# 780-00055_rev1_Pg1_SCH_NRES_Temp_Meas_8-.net
KiCad netlist of a schematic drawn in Altium Designer
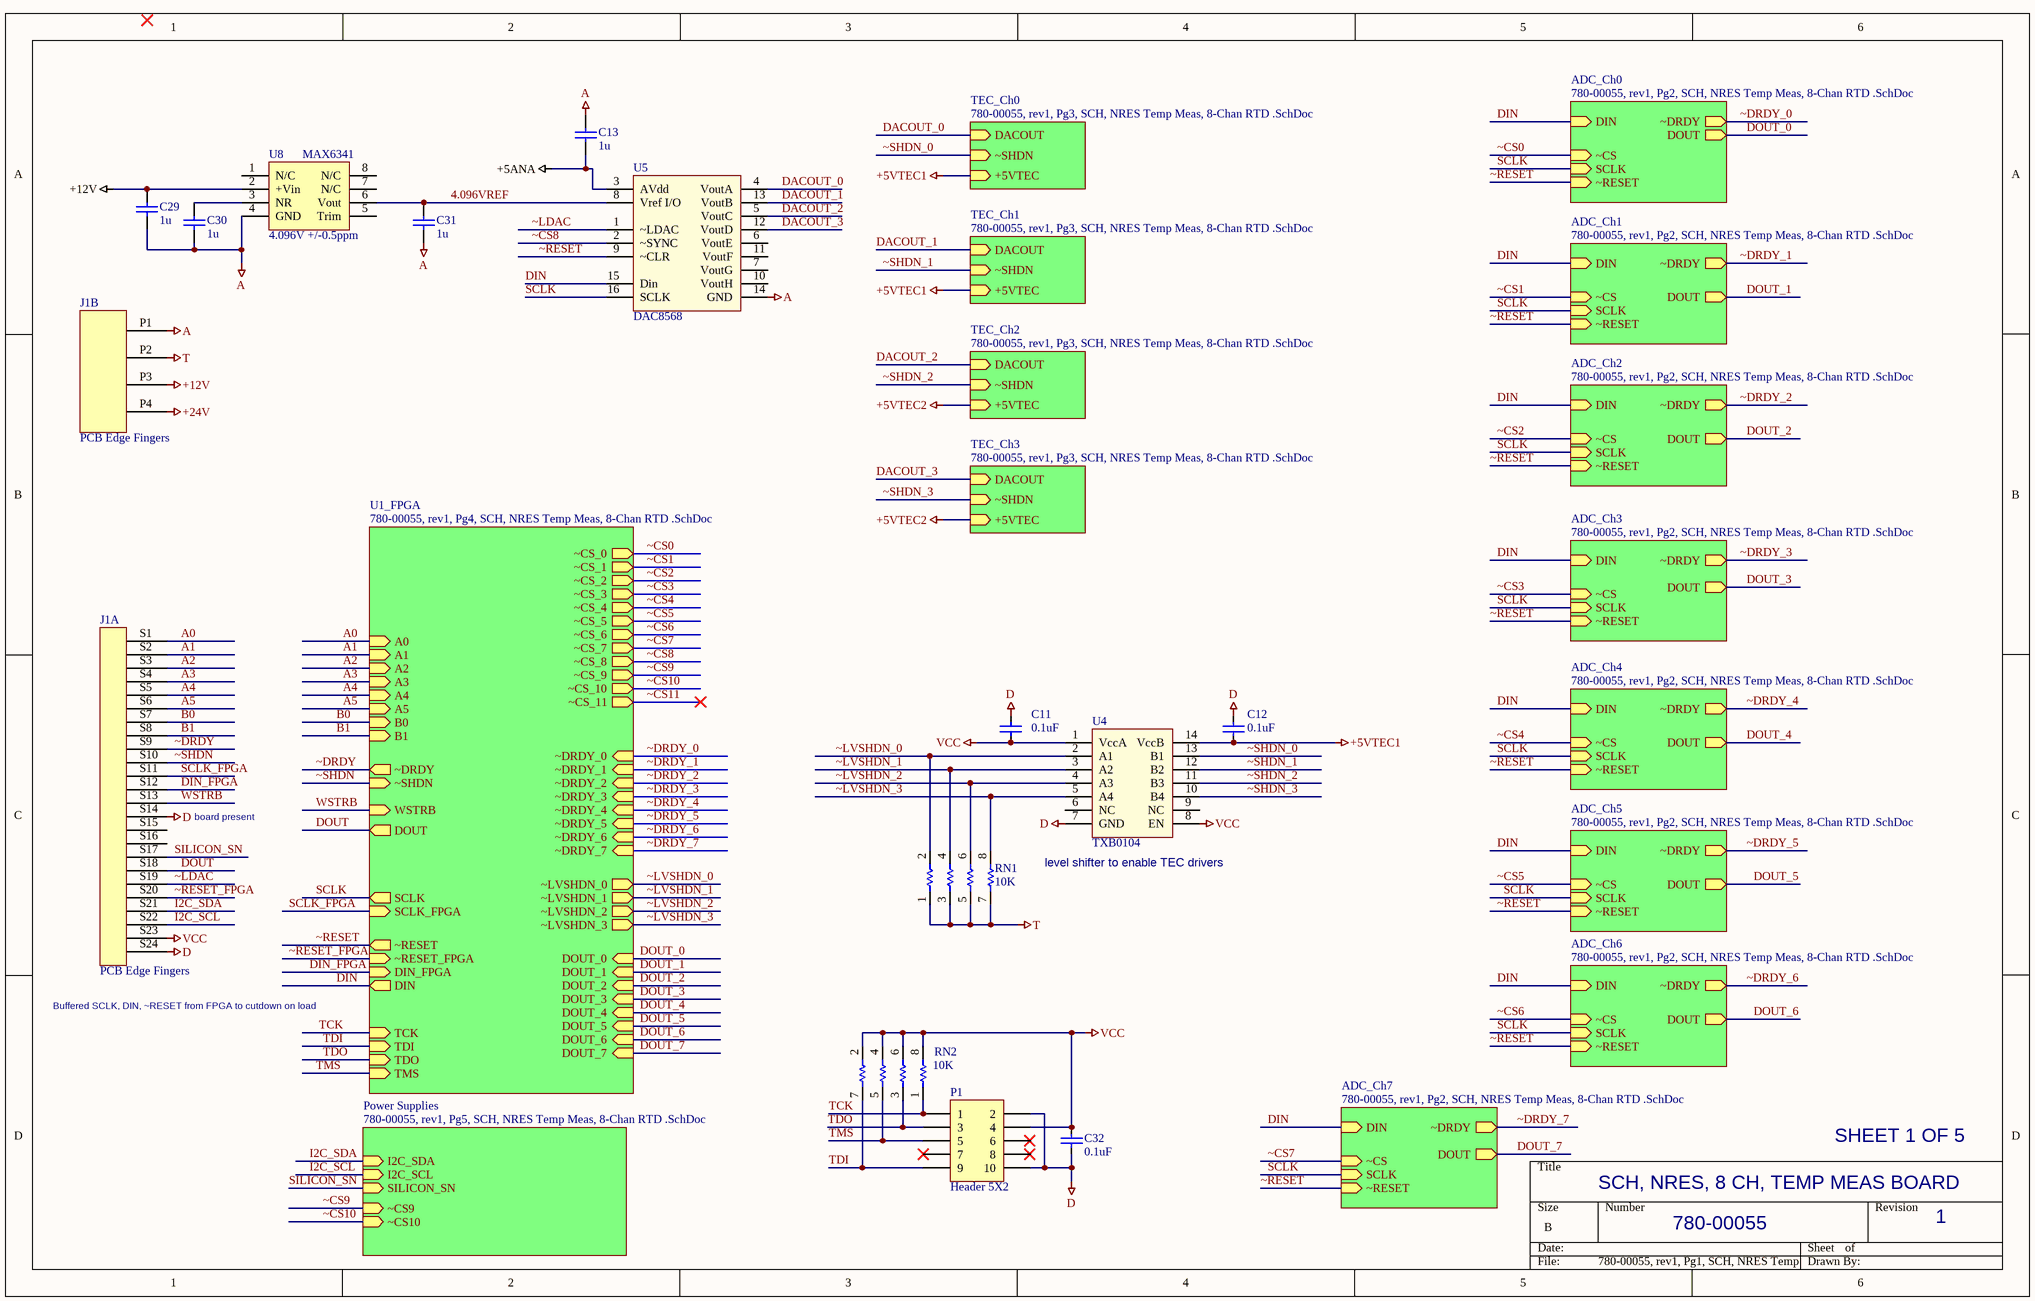
[diagram p0: 780-00055, rev1, Pg1, SCH, NRES Temp Meas, 8-Chan RTD .SchDoc]

(export (version "E")
  (design (tool "Eeschema 10.0.6"))
  (components
    (comp (ref "C11")
      (value "0.1uF")
      (footprint "SMD_0805")
      (description "Capacitor")
      (fields (field (name "Comment") "Cap SMD"))
      (libsource (lib "Richs Schematic Components") (part "Cap SMD"))
    )
    (comp (ref "C12")
      (value "0.1uF")
      (footprint "SMD_0805")
      (description "Capacitor")
      (fields (field (name "Comment") "Cap SMD"))
      (libsource (lib "Richs Schematic Components") (part "Cap SMD"))
    )
    (comp (ref "C13")
      (value "1u")
      (footprint "SMD_0805")
      (description "Capacitor")
      (fields (field (name "MANUFACTURER") "Taiyo Yuden"))
      (libsource (lib "Miscellaneous Devices") (part "Cap"))
    )
    (comp (ref "C29")
      (value "1u")
      (footprint "SMD_0805")
      (description "Capacitor")
      (fields (field (name "MANUFACTURER") "Taiyo Yuden"))
      (libsource (lib "Miscellaneous Devices") (part "Cap"))
    )
    (comp (ref "C30")
      (value "1u")
      (footprint "SMD_0805")
      (description "Capacitor")
      (fields (field (name "MANUFACTURER") "Taiyo Yuden"))
      (libsource (lib "Miscellaneous Devices") (part "Cap"))
    )
    (comp (ref "C31")
      (value "1u")
      (footprint "SMD_0805")
      (description "Capacitor")
      (fields (field (name "MANUFACTURER") "Taiyo Yuden"))
      (libsource (lib "Miscellaneous Devices") (part "Cap"))
    )
    (comp (ref "C32")
      (value "0.1uF")
      (footprint "SMD_0805")
      (description "Capacitor")
      (fields (field (name "MANUFACTURER") "AVX") (field (name "Comment") "Cap SMD"))
      (libsource (lib "Richs Schematic Components") (part "Cap SMD"))
    )
    (comp (ref "J1")
      (value "PCB Edge Fingers")
      (footprint "PCB EDGE, MOLEX 46114")
      (description "PCB Edge Conn to fit Molex 46114 backplane connector")
      (libsource (lib "Richs Schematic Components") (part "Conn, PCB Card Edge / Molex 46114, 24 sig / 4 pwr"))
    )
    (comp (ref "P1")
      (value "Header 5X2")
      (footprint "HDR2X5")
      (description "Header, 5-Pin, Dual row")
      (fields (field (name "MANUFACTURER") "FCI"))
      (libsource (lib "Miscellaneous Connectors") (part "Header 5X2"))
    )
    (comp (ref "RN1")
      (value "10K")
      (footprint "RES ARRAY 0603 x 4")
      (description "Resistor Array 4 Isolated")
      (fields (field (name "MANUFACTURER") "PANASONIC - ECG") (field (name "Comment") "RES ARRAY  x4 10K"))
      (libsource (lib "Richs Schematic Components") (part "RES ARRAY  x4 10K"))
    )
    (comp (ref "RN2")
      (value "10K")
      (footprint "RES ARRAY 0603 x 4")
      (description "Resistor Array 4 Isolated")
      (fields (field (name "MANUFACTURER") "Panasonic ECG") (field (name "Comment") "RES ARRAY  x4"))
      (libsource (lib "Richs Schematic Components") (part "RES ARRAY  x4"))
    )
    (comp (ref "U4")
      (value "TXB0104")
      (footprint "TSSOP14")
      (description "4-Chan Logic Level Shifter Bi-directional")
      (fields (field (name "MANUFACTURER") "TI"))
      (libsource (lib "Richs Schematic Components") (part "TXB0104"))
    )
    (comp (ref "U5")
      (value "DAC8568")
      (footprint "TSSOP16")
      (description "8 Chan, 16-bit DAC, SPI Interface")
      (fields (field (name "MANUFACTURER") "TI"))
      (libsource (lib "Richs Schematic Components") (part "DAC8568"))
    )
    (comp (ref "U8")
      (value "4.096V +/-0.5ppm")
      (footprint "SO-8_M")
      (description "VREF 4.096V 0.5ppm")
      (fields (field (name "MANUFACTURER") "MAXIM") (field (name "ALTIUM_VALUE") "MAX6341"))
      (libsource (lib "Richs Schematic Components") (part "MAX6341"))
    )
  )
  (nets
    (net (code "1") (name "+5ANA") (class "Default")
      (node (ref "C13") (pin "2") (pinfunction "2_2") (pintype "passive"))
      (node (ref "U5") (pin "3") (pinfunction "AVdd_3") (pintype "passive"))
    )
    (net (code "2") (name "+5VTEC1") (class "Default")
      (node (ref "C12") (pin "1") (pinfunction "1_1") (pintype "passive"))
      (node (ref "U4") (pin "14") (pinfunction "VccB_14") (pintype "passive"))
    )
    (net (code "4") (name "+12V") (class "Default")
      (node (ref "C29") (pin "1") (pinfunction "1_1") (pintype "passive"))
      (node (ref "J1") (pin "P3") (pinfunction "S27_P3") (pintype "passive"))
      (node (ref "U8") (pin "2") (pinfunction "+Vin_2") (pintype "passive"))
    )
    (net (code "5") (name "+24V") (class "Default")
      (node (ref "J1") (pin "P4") (pinfunction "S28_P4") (pintype "passive"))
    )
    (net (code "6") (name "/4.096VREF") (class "Default")
      (node (ref "C31") (pin "1") (pinfunction "1_1") (pintype "passive"))
      (node (ref "U5") (pin "8") (pinfunction "Vref_I/O_8") (pintype "passive"))
      (node (ref "U8") (pin "6") (pinfunction "Vout_6") (pintype "passive"))
    )
    (net (code "7") (name "/A0") (class "Default") (node (ref "J1") (pin "S1") (pintype "passive")))
    (net (code "8") (name "/A1") (class "Default") (node (ref "J1") (pin "S2") (pintype "passive")))
    (net (code "9") (name "/A2") (class "Default") (node (ref "J1") (pin "S3") (pintype "passive")))
    (net (code "10") (name "/A3") (class "Default") (node (ref "J1") (pin "S4") (pintype "passive")))
    (net (code "11") (name "/A4") (class "Default") (node (ref "J1") (pin "S5") (pintype "passive")))
    (net (code "12") (name "/A5") (class "Default") (node (ref "J1") (pin "S6") (pintype "passive")))
    (net (code "13") (name "/B0") (class "Default") (node (ref "J1") (pin "S7") (pintype "passive")))
    (net (code "14") (name "/B1") (class "Default") (node (ref "J1") (pin "S8") (pintype "passive")))
    (net (code "15") (name "/DACOUT_0") (class "Default")
      (node (ref "U5") (pin "4") (pinfunction "VoutA_4") (pintype "passive"))
    )
    (net (code "16") (name "/DACOUT_1") (class "Default")
      (node (ref "U5") (pin "13") (pinfunction "VoutB_13") (pintype "passive"))
    )
    (net (code "17") (name "/DACOUT_2") (class "Default")
      (node (ref "U5") (pin "5") (pinfunction "VoutC_5") (pintype "passive"))
    )
    (net (code "18") (name "/DACOUT_3") (class "Default")
      (node (ref "U5") (pin "12") (pinfunction "VoutD_12") (pintype "passive"))
    )
    (net (code "19") (name "/DIN") (class "Default")
      (node (ref "U5") (pin "15") (pinfunction "Din_15") (pintype "passive"))
    )
    (net (code "20") (name "/DIN_FPGA") (class "Default") (node (ref "J1") (pin "S12") (pintype "passive")))
    (net (code "21") (name "/DOUT") (class "Default") (node (ref "J1") (pin "S18") (pintype "passive")))
    (net (code "30") (name "/I2C_SCL") (class "Default") (node (ref "J1") (pin "S22") (pintype "passive")))
    (net (code "31") (name "/I2C_SDA") (class "Default") (node (ref "J1") (pin "S21") (pintype "passive")))
    (net (code "32") (name "/SCLK") (class "Default")
      (node (ref "U5") (pin "16") (pinfunction "SCLK_16") (pintype "passive"))
    )
    (net (code "33") (name "/SCLK_FPGA") (class "Default") (node (ref "J1") (pin "S11") (pintype "passive")))
    (net (code "34") (name "/SILICON_SN") (class "Default") (node (ref "J1") (pin "S17") (pintype "passive")))
    (net (code "35") (name "/TCK") (class "Default")
      (node (ref "P1") (pin "1") (pinfunction "1_1") (pintype "passive"))
      (node (ref "RN2") (pin "1") (pinfunction "1_1") (pintype "passive"))
    )
    (net (code "36") (name "/TDI") (class "Default")
      (node (ref "P1") (pin "9") (pinfunction "9_9") (pintype "passive"))
      (node (ref "RN2") (pin "7") (pinfunction "1_7") (pintype "passive"))
    )
    (net (code "37") (name "/TDO") (class "Default")
      (node (ref "P1") (pin "3") (pinfunction "3_3") (pintype "passive"))
      (node (ref "RN2") (pin "3") (pinfunction "3_3") (pintype "passive"))
    )
    (net (code "38") (name "/TMS") (class "Default")
      (node (ref "P1") (pin "5") (pinfunction "5_5") (pintype "passive"))
      (node (ref "RN2") (pin "5") (pinfunction "5_5") (pintype "passive"))
    )
    (net (code "39") (name "/WSTRB") (class "Default") (node (ref "J1") (pin "S13") (pintype "passive")))
    (net (code "48") (name "/~CS8") (class "Default")
      (node (ref "U5") (pin "2") (pinfunction "~SYNC_2") (pintype "passive"))
    )
    (net (code "52") (name "/~DRDY") (class "Default") (node (ref "J1") (pin "S9") (pintype "passive")))
    (net (code "61") (name "/~LDAC") (class "Default")
      (node (ref "J1") (pin "S19") (pintype "passive"))
      (node (ref "U5") (pin "1") (pinfunction "~LDAC_1") (pintype "passive"))
    )
    (net (code "62") (name "/~LVSHDN_0") (class "Default")
      (node (ref "RN1") (pin "2") (pinfunction "2_2") (pintype "passive"))
      (node (ref "U4") (pin "2") (pinfunction "A1_2") (pintype "passive"))
    )
    (net (code "63") (name "/~LVSHDN_1") (class "Default")
      (node (ref "RN1") (pin "4") (pinfunction "4_4") (pintype "passive"))
      (node (ref "U4") (pin "3") (pinfunction "A2_3") (pintype "passive"))
    )
    (net (code "64") (name "/~LVSHDN_2") (class "Default")
      (node (ref "RN1") (pin "6") (pinfunction "6_6") (pintype "passive"))
      (node (ref "U4") (pin "4") (pinfunction "A3_4") (pintype "passive"))
    )
    (net (code "65") (name "/~LVSHDN_3") (class "Default")
      (node (ref "RN1") (pin "8") (pinfunction "8_8") (pintype "passive"))
      (node (ref "U4") (pin "5") (pinfunction "A4_5") (pintype "passive"))
    )
    (net (code "66") (name "/~RESET") (class "Default")
      (node (ref "U5") (pin "9") (pinfunction "~CLR_9") (pintype "passive"))
    )
    (net (code "67") (name "/~RESET_FPGA") (class "Default")
      (node (ref "J1") (pin "S20") (pintype "passive"))
    )
    (net (code "68") (name "/~SHDN") (class "Default") (node (ref "J1") (pin "S10") (pintype "passive")))
    (net (code "69") (name "/~SHDN_0") (class "Default")
      (node (ref "U4") (pin "13") (pinfunction "B1_13") (pintype "passive"))
    )
    (net (code "70") (name "/~SHDN_1") (class "Default")
      (node (ref "U4") (pin "12") (pinfunction "B2_12") (pintype "passive"))
    )
    (net (code "71") (name "/~SHDN_2") (class "Default")
      (node (ref "U4") (pin "11") (pinfunction "B3_11") (pintype "passive"))
    )
    (net (code "72") (name "/~SHDN_3") (class "Default")
      (node (ref "U4") (pin "10") (pinfunction "B4_10") (pintype "passive"))
    )
    (net (code "73") (name "A") (class "Default")
      (node (ref "C13") (pin "1") (pinfunction "1_1") (pintype "passive"))
      (node (ref "C29") (pin "2") (pinfunction "2_2") (pintype "passive"))
      (node (ref "C30") (pin "2") (pinfunction "2_2") (pintype "passive"))
      (node (ref "C31") (pin "2") (pinfunction "2_2") (pintype "passive"))
      (node (ref "J1") (pin "P1") (pinfunction "S25_P1") (pintype "passive"))
      (node (ref "U5") (pin "14") (pinfunction "GND_14") (pintype "passive"))
      (node (ref "U8") (pin "4") (pinfunction "GND_4") (pintype "passive"))
    )
    (net (code "74") (name "D") (class "Default")
      (node (ref "C11") (pin "2") (pinfunction "2_2") (pintype "passive"))
      (node (ref "C12") (pin "2") (pinfunction "2_2") (pintype "passive"))
      (node (ref "C32") (pin "1") (pinfunction "1_1") (pintype "passive"))
      (node (ref "J1") (pin "S14") (pintype "passive"))
      (node (ref "J1") (pin "S24") (pintype "passive"))
      (node (ref "P1") (pin "10") (pinfunction "10_10") (pintype "passive"))
      (node (ref "P1") (pin "2") (pinfunction "2_2") (pintype "passive"))
      (node (ref "U4") (pin "7") (pinfunction "GND_7") (pintype "passive"))
    )
    (net (code "75") (name "Net-(U8-NR)") (class "Default")
      (node (ref "C30") (pin "1") (pinfunction "1_1") (pintype "passive"))
      (node (ref "U8") (pin "3") (pinfunction "NR_3") (pintype "passive"))
    )
    (net (code "76") (name "T") (class "Default")
      (node (ref "J1") (pin "P2") (pinfunction "S26_P2") (pintype "passive"))
      (node (ref "RN1") (pin "1") (pinfunction "1_1") (pintype "passive"))
      (node (ref "RN1") (pin "3") (pinfunction "3_3") (pintype "passive"))
      (node (ref "RN1") (pin "5") (pinfunction "5_5") (pintype "passive"))
      (node (ref "RN1") (pin "7") (pinfunction "1_7") (pintype "passive"))
    )
    (net (code "77") (name "VCC") (class "Default")
      (node (ref "C11") (pin "1") (pinfunction "1_1") (pintype "passive"))
      (node (ref "C32") (pin "2") (pinfunction "2_2") (pintype "passive"))
      (node (ref "J1") (pin "S23") (pintype "passive"))
      (node (ref "P1") (pin "4") (pinfunction "4_4") (pintype "passive"))
      (node (ref "RN2") (pin "2") (pinfunction "2_2") (pintype "passive"))
      (node (ref "RN2") (pin "4") (pinfunction "4_4") (pintype "passive"))
      (node (ref "RN2") (pin "6") (pinfunction "6_6") (pintype "passive"))
      (node (ref "RN2") (pin "8") (pinfunction "8_8") (pintype "passive"))
      (node (ref "U4") (pin "1") (pinfunction "VccA_1") (pintype "passive"))
      (node (ref "U4") (pin "8") (pinfunction "EN_8") (pintype "passive"))
    )
    (net (code "78") (name "unconnected-(J1-PadS15)") (class "Default")
      (node (ref "J1") (pin "S15") (pintype "passive"))
    )
    (net (code "79") (name "unconnected-(J1-PadS16)") (class "Default")
      (node (ref "J1") (pin "S16") (pintype "passive"))
    )
    (net (code "80") (name "unconnected-(P1-Pad6)") (class "Default")
      (node (ref "P1") (pin "6") (pinfunction "6_6") (pintype "passive"))
    )
    (net (code "81") (name "unconnected-(P1-Pad7)") (class "Default")
      (node (ref "P1") (pin "7") (pinfunction "7_7") (pintype "passive+no_connect"))
    )
    (net (code "82") (name "unconnected-(P1-Pad8)") (class "Default")
      (node (ref "P1") (pin "8") (pinfunction "8_8") (pintype "passive"))
    )
    (net (code "83") (name "unconnected-(U4-NC-Pad6)") (class "Default")
      (node (ref "U4") (pin "6") (pinfunction "NC_6") (pintype "passive"))
    )
    (net (code "84") (name "unconnected-(U4-NC-Pad9)") (class "Default")
      (node (ref "U4") (pin "9") (pinfunction "NC_9") (pintype "passive"))
    )
    (net (code "85") (name "unconnected-(U5-VoutE-Pad6)") (class "Default")
      (node (ref "U5") (pin "6") (pinfunction "VoutE_6") (pintype "passive"))
    )
    (net (code "86") (name "unconnected-(U5-VoutF-Pad11)") (class "Default")
      (node (ref "U5") (pin "11") (pinfunction "VoutF_11") (pintype "passive"))
    )
    (net (code "87") (name "unconnected-(U5-VoutG-Pad7)") (class "Default")
      (node (ref "U5") (pin "7") (pinfunction "VoutG_7") (pintype "passive"))
    )
    (net (code "88") (name "unconnected-(U5-VoutH-Pad10)") (class "Default")
      (node (ref "U5") (pin "10") (pinfunction "VoutH_10") (pintype "passive"))
    )
    (net (code "89") (name "unconnected-(U8-N{slash}C-Pad1)") (class "Default")
      (node (ref "U8") (pin "1") (pinfunction "N/C_1") (pintype "passive"))
    )
    (net (code "90") (name "unconnected-(U8-N{slash}C-Pad7)") (class "Default")
      (node (ref "U8") (pin "7") (pinfunction "N/C_7") (pintype "passive"))
    )
    (net (code "91") (name "unconnected-(U8-N{slash}C-Pad8)") (class "Default")
      (node (ref "U8") (pin "8") (pinfunction "N/C_8") (pintype "passive"))
    )
    (net (code "92") (name "unconnected-(U8-Trim-Pad5)") (class "Default")
      (node (ref "U8") (pin "5") (pinfunction "Trim_5") (pintype "passive"))
    )
  )
)
